# relay_driver.net
KiCad netlist of a schematic drawn in Altium Designer
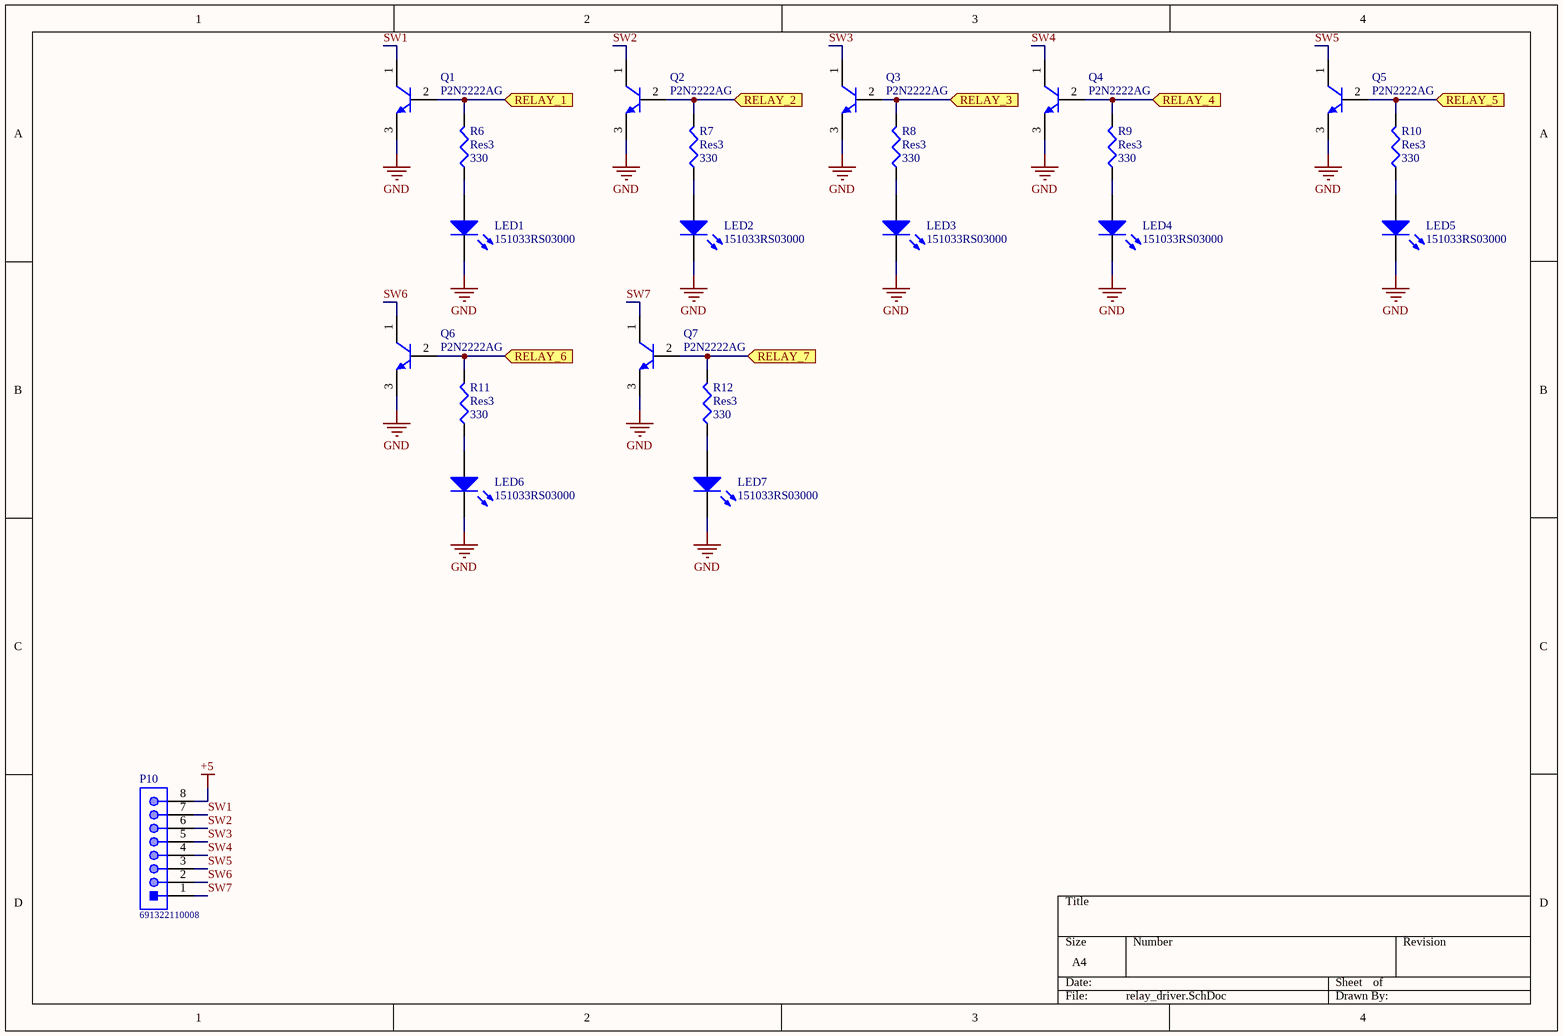
[diagram p0: relay_driver.SchDoc]

(export (version "E")
  (design (tool "Eeschema 10.0.6"))
  (components
    (comp (ref "LED1")
      (value "151033RS03000")
      (footprint "Type 3mm")
      (description "THT LED round mono-color waterclear, WL-TMRW, Red")
      (fields (field (name "MANUFACTURER") "Wuerth Elektronik"))
      (libsource (lib "Altium Content Vault") (part "WE-LED_K1A2-2"))
    )
    (comp (ref "LED2")
      (value "151033RS03000")
      (footprint "Type 3mm")
      (description "THT LED round mono-color waterclear, WL-TMRW, Red")
      (fields (field (name "MANUFACTURER") "Wuerth Elektronik"))
      (libsource (lib "Altium Content Vault") (part "WE-LED_K1A2-2"))
    )
    (comp (ref "LED3")
      (value "151033RS03000")
      (footprint "Type 3mm")
      (description "THT LED round mono-color waterclear, WL-TMRW, Red")
      (fields (field (name "MANUFACTURER") "Wuerth Elektronik"))
      (libsource (lib "Altium Content Vault") (part "WE-LED_K1A2-2"))
    )
    (comp (ref "LED4")
      (value "151033RS03000")
      (footprint "Type 3mm")
      (description "THT LED round mono-color waterclear, WL-TMRW, Red")
      (fields (field (name "MANUFACTURER") "Wuerth Elektronik"))
      (libsource (lib "Altium Content Vault") (part "WE-LED_K1A2-2"))
    )
    (comp (ref "LED5")
      (value "151033RS03000")
      (footprint "Type 3mm")
      (description "THT LED round mono-color waterclear, WL-TMRW, Red")
      (fields (field (name "MANUFACTURER") "Wuerth Elektronik"))
      (libsource (lib "Altium Content Vault") (part "WE-LED_K1A2-2"))
    )
    (comp (ref "LED6")
      (value "151033RS03000")
      (footprint "Type 3mm")
      (description "THT LED round mono-color waterclear, WL-TMRW, Red")
      (fields (field (name "MANUFACTURER") "Wuerth Elektronik"))
      (libsource (lib "Altium Content Vault") (part "WE-LED_K1A2-2"))
    )
    (comp (ref "LED7")
      (value "151033RS03000")
      (footprint "Type 3mm")
      (description "THT LED round mono-color waterclear, WL-TMRW, Red")
      (fields (field (name "MANUFACTURER") "Wuerth Elektronik"))
      (libsource (lib "Altium Content Vault") (part "WE-LED_K1A2-2"))
    )
    (comp (ref "P10")
      (value "691322110008")
      (footprint "691322110008")
      (description "Serie 3221 - 3.50mm Horizontal PCB Header WR-TBL, 8 pin")
      (fields (field (name "MANUFACTURER") "Wurth Elektronik") (field (name "PUBLISHER") "WurthElektronik"))
      (libsource (lib "Altium Content Vault") (part "WE-CN-1P-M-R8"))
    )
    (comp (ref "Q1")
      (value "P2N2222AG")
      (footprint "ONSC-TO-92-3-29-11")
      (description "Amplifier Transistor, NPN Silicon, 3-Pin TO-92, Pb-Free, Bulk Box")
      (fields (field (name "MANUFACTURER") "On Semiconductor"))
      (libsource (lib "Altium Content Vault") (part "ONSC-NPN-C1B2E3-3"))
    )
    (comp (ref "Q2")
      (value "P2N2222AG")
      (footprint "ONSC-TO-92-3-29-11")
      (description "Amplifier Transistor, NPN Silicon, 3-Pin TO-92, Pb-Free, Bulk Box")
      (fields (field (name "MANUFACTURER") "On Semiconductor"))
      (libsource (lib "Altium Content Vault") (part "ONSC-NPN-C1B2E3-3"))
    )
    (comp (ref "Q3")
      (value "P2N2222AG")
      (footprint "ONSC-TO-92-3-29-11")
      (description "Amplifier Transistor, NPN Silicon, 3-Pin TO-92, Pb-Free, Bulk Box")
      (fields (field (name "MANUFACTURER") "On Semiconductor"))
      (libsource (lib "Altium Content Vault") (part "ONSC-NPN-C1B2E3-3"))
    )
    (comp (ref "Q4")
      (value "P2N2222AG")
      (footprint "ONSC-TO-92-3-29-11")
      (description "Amplifier Transistor, NPN Silicon, 3-Pin TO-92, Pb-Free, Bulk Box")
      (fields (field (name "MANUFACTURER") "On Semiconductor"))
      (libsource (lib "Altium Content Vault") (part "ONSC-NPN-C1B2E3-3"))
    )
    (comp (ref "Q5")
      (value "P2N2222AG")
      (footprint "ONSC-TO-92-3-29-11")
      (description "Amplifier Transistor, NPN Silicon, 3-Pin TO-92, Pb-Free, Bulk Box")
      (fields (field (name "MANUFACTURER") "On Semiconductor"))
      (libsource (lib "Altium Content Vault") (part "ONSC-NPN-C1B2E3-3"))
    )
    (comp (ref "Q6")
      (value "P2N2222AG")
      (footprint "ONSC-TO-92-3-29-11")
      (description "Amplifier Transistor, NPN Silicon, 3-Pin TO-92, Pb-Free, Bulk Box")
      (fields (field (name "MANUFACTURER") "On Semiconductor"))
      (libsource (lib "Altium Content Vault") (part "ONSC-NPN-C1B2E3-3"))
    )
    (comp (ref "Q7")
      (value "P2N2222AG")
      (footprint "ONSC-TO-92-3-29-11")
      (description "Amplifier Transistor, NPN Silicon, 3-Pin TO-92, Pb-Free, Bulk Box")
      (fields (field (name "MANUFACTURER") "On Semiconductor"))
      (libsource (lib "Altium Content Vault") (part "ONSC-NPN-C1B2E3-3"))
    )
    (comp (ref "R6")
      (value "Res3")
      (footprint "AXIAL-0.3")
      (description "Resistor")
      (fields (field (name "ALTIUM_VALUE") "330") (field (name "PUBLISHER") "Altium Limited"))
      (libsource (lib "Miscellaneous Devices") (part "Res3"))
    )
    (comp (ref "R7")
      (value "Res3")
      (footprint "AXIAL-0.3")
      (description "Resistor")
      (fields (field (name "ALTIUM_VALUE") "330") (field (name "PUBLISHER") "Altium Limited"))
      (libsource (lib "Miscellaneous Devices") (part "Res3"))
    )
    (comp (ref "R8")
      (value "Res3")
      (footprint "AXIAL-0.3")
      (description "Resistor")
      (fields (field (name "ALTIUM_VALUE") "330") (field (name "PUBLISHER") "Altium Limited"))
      (libsource (lib "Miscellaneous Devices") (part "Res3"))
    )
    (comp (ref "R9")
      (value "Res3")
      (footprint "AXIAL-0.3")
      (description "Resistor")
      (fields (field (name "ALTIUM_VALUE") "330") (field (name "PUBLISHER") "Altium Limited"))
      (libsource (lib "Miscellaneous Devices") (part "Res3"))
    )
    (comp (ref "R10")
      (value "Res3")
      (footprint "AXIAL-0.3")
      (description "Resistor")
      (fields (field (name "ALTIUM_VALUE") "330") (field (name "PUBLISHER") "Altium Limited"))
      (libsource (lib "Miscellaneous Devices") (part "Res3"))
    )
    (comp (ref "R11")
      (value "Res3")
      (footprint "AXIAL-0.3")
      (description "Resistor")
      (fields (field (name "ALTIUM_VALUE") "330") (field (name "PUBLISHER") "Altium Limited"))
      (libsource (lib "Miscellaneous Devices") (part "Res3"))
    )
    (comp (ref "R12")
      (value "Res3")
      (footprint "AXIAL-0.3")
      (description "Resistor")
      (fields (field (name "ALTIUM_VALUE") "330") (field (name "PUBLISHER") "Altium Limited"))
      (libsource (lib "Miscellaneous Devices") (part "Res3"))
    )
  )
  (nets
    (net (code "1") (name "+5") (class "Default")
      (node (ref "P10") (pin "8") (pinfunction "8_8") (pintype "passive"))
    )
    (net (code "2") (name "/RELAY_1") (class "Default")
      (node (ref "Q1") (pin "2") (pinfunction "B_2") (pintype "passive"))
      (node (ref "R6") (pin "2") (pinfunction "2_2") (pintype "passive"))
    )
    (net (code "3") (name "/RELAY_2") (class "Default")
      (node (ref "Q2") (pin "2") (pinfunction "B_2") (pintype "passive"))
      (node (ref "R7") (pin "2") (pinfunction "2_2") (pintype "passive"))
    )
    (net (code "4") (name "/RELAY_3") (class "Default")
      (node (ref "Q3") (pin "2") (pinfunction "B_2") (pintype "passive"))
      (node (ref "R8") (pin "2") (pinfunction "2_2") (pintype "passive"))
    )
    (net (code "5") (name "/RELAY_4") (class "Default")
      (node (ref "Q4") (pin "2") (pinfunction "B_2") (pintype "passive"))
      (node (ref "R9") (pin "2") (pinfunction "2_2") (pintype "passive"))
    )
    (net (code "6") (name "/RELAY_5") (class "Default")
      (node (ref "Q5") (pin "2") (pinfunction "B_2") (pintype "passive"))
      (node (ref "R10") (pin "2") (pinfunction "2_2") (pintype "passive"))
    )
    (net (code "7") (name "/RELAY_6") (class "Default")
      (node (ref "Q6") (pin "2") (pinfunction "B_2") (pintype "passive"))
      (node (ref "R11") (pin "2") (pinfunction "2_2") (pintype "passive"))
    )
    (net (code "8") (name "/RELAY_7") (class "Default")
      (node (ref "Q7") (pin "2") (pinfunction "B_2") (pintype "passive"))
      (node (ref "R12") (pin "2") (pinfunction "2_2") (pintype "passive"))
    )
    (net (code "9") (name "/SW1") (class "Default")
      (node (ref "P10") (pin "7") (pinfunction "7_7") (pintype "passive"))
      (node (ref "Q1") (pin "1") (pinfunction "C_1") (pintype "passive"))
    )
    (net (code "10") (name "/SW2") (class "Default")
      (node (ref "P10") (pin "6") (pinfunction "6_6") (pintype "passive"))
      (node (ref "Q2") (pin "1") (pinfunction "C_1") (pintype "passive"))
    )
    (net (code "11") (name "/SW3") (class "Default")
      (node (ref "P10") (pin "5") (pinfunction "5_5") (pintype "passive"))
      (node (ref "Q3") (pin "1") (pinfunction "C_1") (pintype "passive"))
    )
    (net (code "12") (name "/SW4") (class "Default")
      (node (ref "P10") (pin "4") (pinfunction "4_4") (pintype "passive"))
      (node (ref "Q4") (pin "1") (pinfunction "C_1") (pintype "passive"))
    )
    (net (code "13") (name "/SW5") (class "Default")
      (node (ref "P10") (pin "3") (pinfunction "3_3") (pintype "passive"))
      (node (ref "Q5") (pin "1") (pinfunction "C_1") (pintype "passive"))
    )
    (net (code "14") (name "/SW6") (class "Default")
      (node (ref "P10") (pin "2") (pinfunction "2_2") (pintype "passive"))
      (node (ref "Q6") (pin "1") (pinfunction "C_1") (pintype "passive"))
    )
    (net (code "15") (name "/SW7") (class "Default")
      (node (ref "P10") (pin "1") (pinfunction "1_1") (pintype "passive"))
      (node (ref "Q7") (pin "1") (pinfunction "C_1") (pintype "passive"))
    )
    (net (code "16") (name "GND") (class "Default")
      (node (ref "LED1") (pin "1") (pinfunction "K_1") (pintype "passive"))
      (node (ref "LED2") (pin "1") (pinfunction "K_1") (pintype "passive"))
      (node (ref "LED3") (pin "1") (pinfunction "K_1") (pintype "passive"))
      (node (ref "LED4") (pin "1") (pinfunction "K_1") (pintype "passive"))
      (node (ref "LED5") (pin "1") (pinfunction "K_1") (pintype "passive"))
      (node (ref "LED6") (pin "1") (pinfunction "K_1") (pintype "passive"))
      (node (ref "LED7") (pin "1") (pinfunction "K_1") (pintype "passive"))
      (node (ref "Q1") (pin "3") (pinfunction "E_3") (pintype "passive"))
      (node (ref "Q2") (pin "3") (pinfunction "E_3") (pintype "passive"))
      (node (ref "Q3") (pin "3") (pinfunction "E_3") (pintype "passive"))
      (node (ref "Q4") (pin "3") (pinfunction "E_3") (pintype "passive"))
      (node (ref "Q5") (pin "3") (pinfunction "E_3") (pintype "passive"))
      (node (ref "Q6") (pin "3") (pinfunction "E_3") (pintype "passive"))
      (node (ref "Q7") (pin "3") (pinfunction "E_3") (pintype "passive"))
    )
    (net (code "17") (name "Net-(LED1-A)") (class "Default")
      (node (ref "LED1") (pin "2") (pinfunction "A_2") (pintype "passive"))
      (node (ref "R6") (pin "1") (pinfunction "1_1") (pintype "passive"))
    )
    (net (code "18") (name "Net-(LED2-A)") (class "Default")
      (node (ref "LED2") (pin "2") (pinfunction "A_2") (pintype "passive"))
      (node (ref "R7") (pin "1") (pinfunction "1_1") (pintype "passive"))
    )
    (net (code "19") (name "Net-(LED3-A)") (class "Default")
      (node (ref "LED3") (pin "2") (pinfunction "A_2") (pintype "passive"))
      (node (ref "R8") (pin "1") (pinfunction "1_1") (pintype "passive"))
    )
    (net (code "20") (name "Net-(LED4-A)") (class "Default")
      (node (ref "LED4") (pin "2") (pinfunction "A_2") (pintype "passive"))
      (node (ref "R9") (pin "1") (pinfunction "1_1") (pintype "passive"))
    )
    (net (code "21") (name "Net-(LED5-A)") (class "Default")
      (node (ref "LED5") (pin "2") (pinfunction "A_2") (pintype "passive"))
      (node (ref "R10") (pin "1") (pinfunction "1_1") (pintype "passive"))
    )
    (net (code "22") (name "Net-(LED6-A)") (class "Default")
      (node (ref "LED6") (pin "2") (pinfunction "A_2") (pintype "passive"))
      (node (ref "R11") (pin "1") (pinfunction "1_1") (pintype "passive"))
    )
    (net (code "23") (name "Net-(LED7-A)") (class "Default")
      (node (ref "LED7") (pin "2") (pinfunction "A_2") (pintype "passive"))
      (node (ref "R12") (pin "1") (pinfunction "1_1") (pintype "passive"))
    )
  )
)
